# Utility_Micro_v157.net
KiCad netlist of a schematic drawn in EAGLE
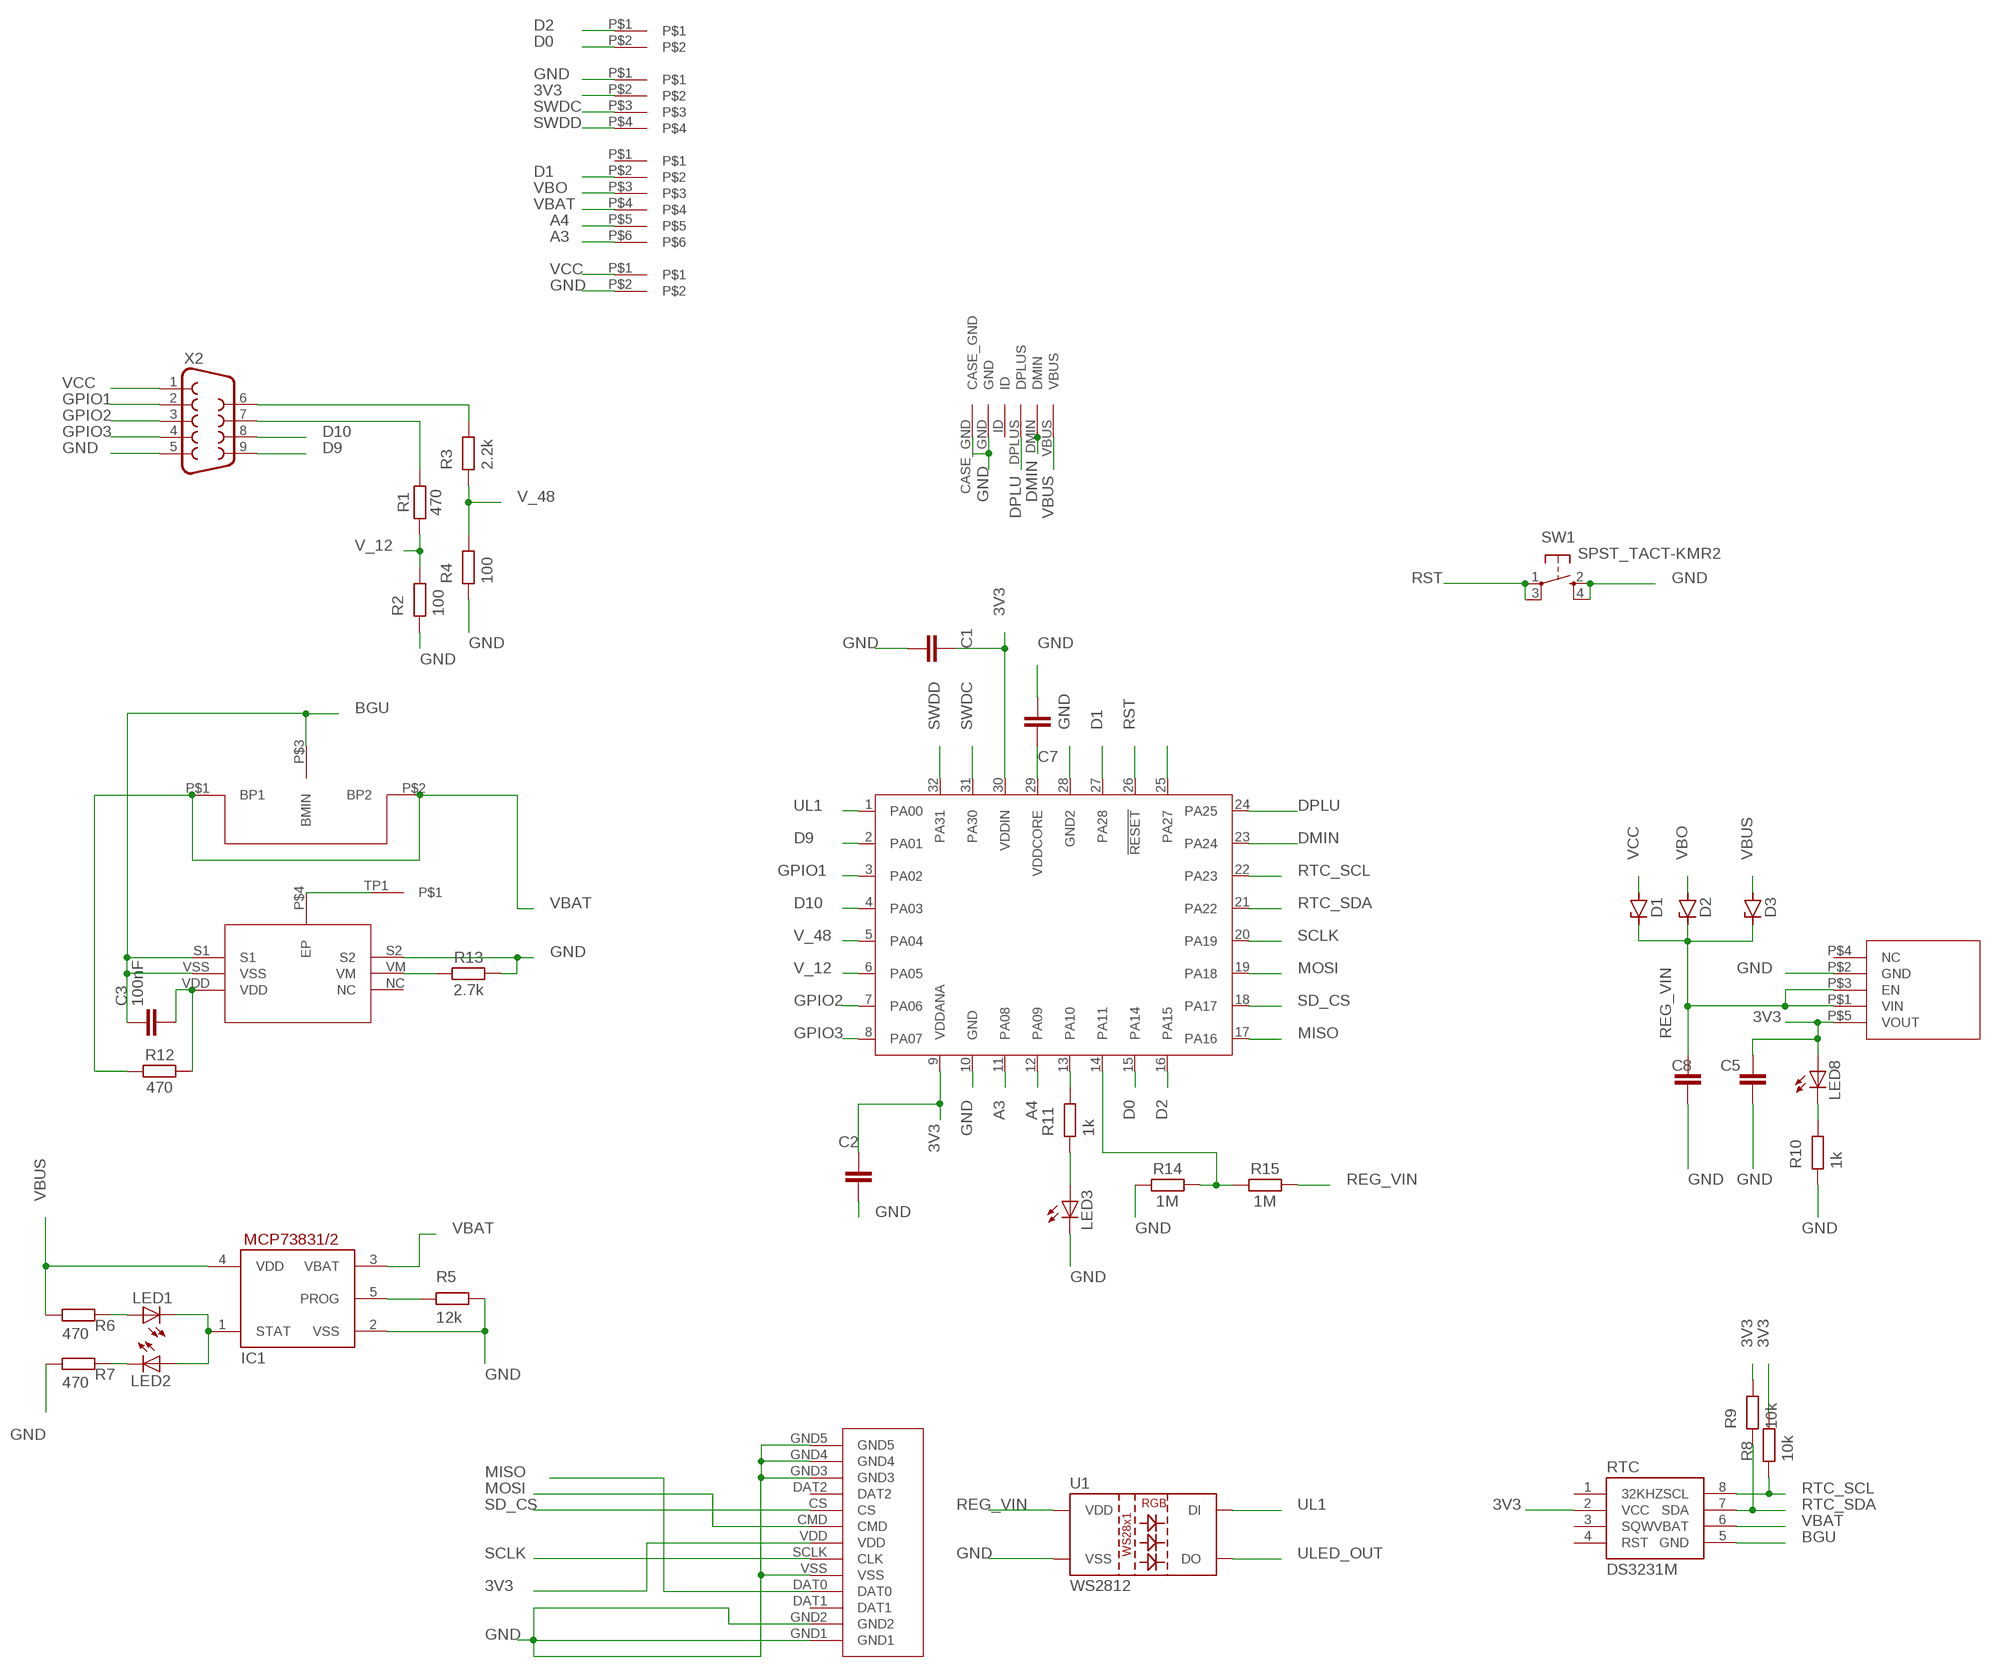
[diagram p0: schematic, sheet 1]

(export (version "E")
  (design (tool "Eeschema 10.0.6"))
  (components
    (comp (ref "ATSAMD21")
      (value "ATSAMD21TQFP")
      (footprint "eagle-import:TQFP32-08")
      (fields (field (name "MANUFACTURER") "Microchip") (field (name "MPN") "ATmega328P"))
      (libsource (lib "eagle-import") (part "ATSAMD21TQFP"))
    )
    (comp (ref "C1")
      (value "100nF")
      (footprint "eagle-import:CAPC1608X85")
      (libsource (lib "eagle-import") (part "CCHIP-0603(1608-METRIC)_"))
    )
    (comp (ref "C2")
      (value "100nF")
      (footprint "eagle-import:CAPC1608X85")
      (libsource (lib "eagle-import") (part "CCHIP-0603(1608-METRIC)_"))
    )
    (comp (ref "C3")
      (value "100nF")
      (footprint "eagle-import:CAPC1608X85")
      (libsource (lib "eagle-import") (part "CCHIP-0603(1608-METRIC)_"))
    )
    (comp (ref "C5")
      (value "10uF")
      (footprint "eagle-import:CAPC1608X85")
      (libsource (lib "eagle-import") (part "CCHIP-0603(1608-METRIC)_"))
    )
    (comp (ref "C7")
      (value "1uF")
      (footprint "eagle-import:CAPC1608X85")
      (libsource (lib "eagle-import") (part "CCHIP-0603(1608-METRIC)_"))
    )
    (comp (ref "C8")
      (value "10uF")
      (footprint "eagle-import:CAPC1608X85")
      (libsource (lib "eagle-import") (part "CCHIP-0603(1608-METRIC)_"))
    )
    (comp (ref "D1")
      (value "SCHOTTKY_MBR0520LT1GDO-219-AB(SOD123F)")
      (footprint "eagle-import:SODFL3718X115")
      (fields (field (name "MANUFACTURER") "ON Semiconductor") (field (name "MPN") "MBR0520LT1G"))
      (libsource (lib "eagle-import") (part "SCHOTTKY_DO-219-AB(SOD123F)MBR0520LT1G"))
    )
    (comp (ref "D2")
      (value "SCHOTTKY_MBR0520LT1GDO-219-AB(SOD123F)")
      (footprint "eagle-import:SODFL3718X115")
      (fields (field (name "MANUFACTURER") "ON Semiconductor") (field (name "MPN") "MBR0520LT1G"))
      (libsource (lib "eagle-import") (part "SCHOTTKY_DO-219-AB(SOD123F)MBR0520LT1G"))
    )
    (comp (ref "D3")
      (value "SCHOTTKY_MBR0520LT1GDO-219-AB(SOD123F)")
      (footprint "eagle-import:SODFL3718X115")
      (fields (field (name "MANUFACTURER") "ON Semiconductor") (field (name "MPN") "MBR0520LT1G"))
      (libsource (lib "eagle-import") (part "SCHOTTKY_DO-219-AB(SOD123F)MBR0520LT1G"))
    )
    (comp (ref "IC1")
      (value "MCP73831/OT")
      (footprint "eagle-import:SOT23-5L")
      (libsource (lib "eagle-import") (part "MCP73831/OT"))
    )
    (comp (ref "LED1")
      (value "LEDCHIP-LED0603")
      (footprint "eagle-import:CHIP-LED0603")
      (libsource (lib "eagle-import") (part "LEDCHIP-LED0603"))
    )
    (comp (ref "LED2")
      (value "LEDCHIP-LED0603")
      (footprint "eagle-import:CHIP-LED0603")
      (libsource (lib "eagle-import") (part "LEDCHIP-LED0603"))
    )
    (comp (ref "LED3")
      (value "LEDCHIP-LED0603")
      (footprint "eagle-import:CHIP-LED0603")
      (libsource (lib "eagle-import") (part "LEDCHIP-LED0603"))
    )
    (comp (ref "LED8")
      (value "LEDCHIP-LED0603")
      (footprint "eagle-import:CHIP-LED0603")
      (libsource (lib "eagle-import") (part "LEDCHIP-LED0603"))
    )
    (comp (ref "R1")
      (value "470")
      (footprint "eagle-import:RESC1608X60")
      (libsource (lib "eagle-import") (part "RCHIP-0603(1608-METRIC)_"))
    )
    (comp (ref "R2")
      (value "100")
      (footprint "eagle-import:RESC1608X60")
      (libsource (lib "eagle-import") (part "RCHIP-0603(1608-METRIC)_"))
    )
    (comp (ref "R3")
      (value "2.2k")
      (footprint "eagle-import:RESC1608X60")
      (libsource (lib "eagle-import") (part "RCHIP-0603(1608-METRIC)_"))
    )
    (comp (ref "R4")
      (value "100")
      (footprint "eagle-import:RESC1608X60")
      (libsource (lib "eagle-import") (part "RCHIP-0603(1608-METRIC)_"))
    )
    (comp (ref "R5")
      (value "12k")
      (footprint "eagle-import:RESC1608X60")
      (libsource (lib "eagle-import") (part "RCHIP-0603(1608-METRIC)_"))
    )
    (comp (ref "R6")
      (value "470")
      (footprint "eagle-import:RESC1608X60")
      (libsource (lib "eagle-import") (part "RCHIP-0603(1608-METRIC)_"))
    )
    (comp (ref "R7")
      (value "470")
      (footprint "eagle-import:RESC1608X60")
      (libsource (lib "eagle-import") (part "RCHIP-0603(1608-METRIC)_"))
    )
    (comp (ref "R8")
      (value "10k")
      (footprint "eagle-import:RESC1608X60")
      (libsource (lib "eagle-import") (part "RCHIP-0603(1608-METRIC)_"))
    )
    (comp (ref "R9")
      (value "10k")
      (footprint "eagle-import:RESC1608X60")
      (libsource (lib "eagle-import") (part "RCHIP-0603(1608-METRIC)_"))
    )
    (comp (ref "R10")
      (value "1k")
      (footprint "eagle-import:RESC1608X60")
      (libsource (lib "eagle-import") (part "RCHIP-0603(1608-METRIC)_"))
    )
    (comp (ref "R11")
      (value "1k")
      (footprint "eagle-import:RESC1608X60")
      (libsource (lib "eagle-import") (part "RCHIP-0603(1608-METRIC)_"))
    )
    (comp (ref "R12")
      (value "470")
      (footprint "eagle-import:RESC1608X60")
      (libsource (lib "eagle-import") (part "Resistor_16378527_RCHIP-0603(1608-METRIC)_"))
    )
    (comp (ref "R13")
      (value "2.7k")
      (footprint "eagle-import:RESC1608X60")
      (libsource (lib "eagle-import") (part "Resistor_16378527_RCHIP-0603(1608-METRIC)_"))
    )
    (comp (ref "R14")
      (value "1M")
      (footprint "eagle-import:RESC1608X60")
      (libsource (lib "eagle-import") (part "Resistor_16378527_RCHIP-0603(1608-METRIC)_"))
    )
    (comp (ref "R15")
      (value "1M")
      (footprint "eagle-import:RESC1608X60")
      (libsource (lib "eagle-import") (part "Resistor_16378527_RCHIP-0603(1608-METRIC)_"))
    )
    (comp (ref "RTC")
      (value "DS3231M")
      (footprint "eagle-import:SO08")
      (libsource (lib "eagle-import") (part "DS3231M"))
    )
    (comp (ref "SW1")
      (value "SPST_TACT-KMR2")
      (footprint "eagle-import:KMR2")
      (libsource (lib "eagle-import") (part "SPST_TACT-KMR2"))
    )
    (comp (ref "U$1")
      (value "AP9221")
      (footprint "eagle-import:AP9221_FOOTPRINT")
      (libsource (lib "eagle-import") (part "AP9221"))
    )
    (comp (ref "U$2")
      (value "MOLEX_MICRO_USB")
      (footprint "eagle-import:MOLEX_MICRO_USB")
      (libsource (lib "eagle-import") (part "MOLEX_MICRO_USB"))
    )
    (comp (ref "U$3")
      (value "AP2112")
      (footprint "eagle-import:SOT-25")
      (libsource (lib "eagle-import") (part "AP2112"))
    )
    (comp (ref "U$4")
      (value "LIR2450H")
      (footprint "eagle-import:BC-2005")
      (libsource (lib "eagle-import") (part "LIR2450H"))
    )
    (comp (ref "U$5")
      (value "TP_SMALL_6_DEVICE")
      (footprint "eagle-import:TP_SMALL_6")
      (libsource (lib "eagle-import") (part "TP_SMALL_6_DEVICE"))
    )
    (comp (ref "U$6")
      (value "SMALL_MICRO_SD")
      (footprint "eagle-import:MICRO_SD_SMALL")
      (libsource (lib "eagle-import") (part "SMALL_MICRO_SD"))
    )
    (comp (ref "U$7")
      (value "TP_2")
      (footprint "eagle-import:TP_2")
      (libsource (lib "eagle-import") (part "TP_2"))
    )
    (comp (ref "U$8")
      (value "TP_SMALL_4_DEVICE")
      (footprint "eagle-import:TP_SMALL_4")
      (libsource (lib "eagle-import") (part "TP_SMALL_4_DEVICE"))
    )
    (comp (ref "U$9")
      (value "TP_2")
      (footprint "eagle-import:TP_2")
      (libsource (lib "eagle-import") (part "TP_2"))
    )
    (comp (ref "U$10")
      (value "SINGLE-SMD")
      (footprint "eagle-import:SINGLE-SMD")
      (libsource (lib "eagle-import") (part "SINGLE-SMD"))
    )
    (comp (ref "U1")
      (value "WS2812")
      (footprint "eagle-import:LED-TRICOLOR-5050-IC")
      (libsource (lib "eagle-import") (part "WS2812{dblquote}"))
    )
    (comp (ref "X2")
      (value "F09D")
      (footprint "eagle-import:F09D")
      (libsource (lib "eagle-import") (part "F09D"))
    )
  )
  (nets
    (net (code "1") (name "/3V3") (class "Default")
      (node (ref "ATSAMD21") (pin "30") (pinfunction "VDDIN_30") (pintype "power_in"))
      (node (ref "ATSAMD21") (pin "9") (pinfunction "VDDANA_9") (pintype "power_in"))
      (node (ref "C1") (pin "2") (pinfunction "2_2") (pintype "passive"))
      (node (ref "C2") (pin "2") (pinfunction "2_2") (pintype "passive"))
      (node (ref "C5") (pin "1") (pinfunction "1_1") (pintype "passive"))
      (node (ref "LED8") (pin "A") (pinfunction "A_A") (pintype "passive"))
      (node (ref "R8") (pin "2") (pinfunction "2_2") (pintype "passive"))
      (node (ref "R9") (pin "2") (pinfunction "2_2") (pintype "passive"))
      (node (ref "RTC") (pin "2") (pinfunction "VCC_2") (pintype "power_in"))
      (node (ref "U$3") (pin "P$5") (pinfunction "VOUT_P$5") (pintype "power_in"))
      (node (ref "U$6") (pin "VDD") (pinfunction "VDD_VDD") (pintype "bidirectional"))
      (node (ref "U$8") (pin "P$2") (pinfunction "P$2_P$2") (pintype "bidirectional"))
    )
    (net (code "2") (name "/A3") (class "Default")
      (node (ref "ATSAMD21") (pin "11") (pinfunction "PA08_11") (pintype "bidirectional"))
      (node (ref "U$5") (pin "P$6") (pinfunction "P$6_P$6") (pintype "bidirectional"))
    )
    (net (code "3") (name "/A4") (class "Default")
      (node (ref "ATSAMD21") (pin "12") (pinfunction "PA09_12") (pintype "bidirectional"))
      (node (ref "U$5") (pin "P$5") (pinfunction "P$5_P$5") (pintype "bidirectional"))
    )
    (net (code "4") (name "/BGU") (class "Default")
      (node (ref "C3") (pin "1") (pinfunction "1_1") (pintype "passive"))
      (node (ref "RTC") (pin "5") (pinfunction "GND_5") (pintype "power_in"))
      (node (ref "U$1") (pin "S1") (pinfunction "S1_S1") (pintype "bidirectional"))
      (node (ref "U$1") (pin "VSS") (pinfunction "VSS_VSS") (pintype "bidirectional"))
      (node (ref "U$4") (pin "P$3") (pinfunction "BMIN_P$3") (pintype "bidirectional"))
    )
    (net (code "5") (name "/D0") (class "Default")
      (node (ref "ATSAMD21") (pin "15") (pinfunction "PA14_15") (pintype "bidirectional"))
      (node (ref "U$7") (pin "P$2") (pinfunction "P$2_P$2") (pintype "bidirectional"))
    )
    (net (code "6") (name "/D1") (class "Default")
      (node (ref "ATSAMD21") (pin "27") (pinfunction "PA28_27") (pintype "bidirectional"))
      (node (ref "U$5") (pin "P$2") (pinfunction "P$2_P$2") (pintype "bidirectional"))
    )
    (net (code "7") (name "/D2") (class "Default")
      (node (ref "ATSAMD21") (pin "16") (pinfunction "PA15_16") (pintype "bidirectional"))
      (node (ref "U$7") (pin "P$1") (pinfunction "P$1_P$1") (pintype "bidirectional"))
    )
    (net (code "8") (name "/D9") (class "Default")
      (node (ref "ATSAMD21") (pin "2") (pinfunction "PA01_2") (pintype "bidirectional"))
      (node (ref "X2") (pin "9") (pinfunction "9_9") (pintype "passive"))
    )
    (net (code "9") (name "/D10") (class "Default")
      (node (ref "ATSAMD21") (pin "4") (pinfunction "PA03_4") (pintype "bidirectional"))
      (node (ref "X2") (pin "8") (pinfunction "8_8") (pintype "passive"))
    )
    (net (code "10") (name "/DMIN") (class "Default")
      (node (ref "ATSAMD21") (pin "23") (pinfunction "PA24_23") (pintype "bidirectional"))
      (node (ref "U$2") (pin "DMIN") (pinfunction "DMIN_DMIN") (pintype "bidirectional"))
    )
    (net (code "11") (name "/DPLU") (class "Default")
      (node (ref "ATSAMD21") (pin "24") (pinfunction "PA25_24") (pintype "bidirectional"))
      (node (ref "U$2") (pin "DPLUS") (pinfunction "DPLUS_DPLUS") (pintype "bidirectional"))
    )
    (net (code "12") (name "/GND") (class "Default")
      (node (ref "ATSAMD21") (pin "10") (pinfunction "GND_10") (pintype "passive"))
      (node (ref "ATSAMD21") (pin "28") (pinfunction "GND2_28") (pintype "passive"))
      (node (ref "C1") (pin "1") (pinfunction "1_1") (pintype "passive"))
      (node (ref "C2") (pin "1") (pinfunction "1_1") (pintype "passive"))
      (node (ref "C5") (pin "2") (pinfunction "2_2") (pintype "passive"))
      (node (ref "C7") (pin "1") (pinfunction "1_1") (pintype "passive"))
      (node (ref "C8") (pin "2") (pinfunction "2_2") (pintype "passive"))
      (node (ref "IC1") (pin "2") (pinfunction "VSS_2") (pintype "power_in"))
      (node (ref "LED3") (pin "C") (pinfunction "C_C") (pintype "passive"))
      (node (ref "R10") (pin "1") (pinfunction "1_1") (pintype "passive"))
      (node (ref "R13") (pin "2") (pinfunction "2_2") (pintype "passive"))
      (node (ref "R14") (pin "1") (pinfunction "1_1") (pintype "passive"))
      (node (ref "R2") (pin "1") (pinfunction "1_1") (pintype "passive"))
      (node (ref "R4") (pin "1") (pinfunction "1_1") (pintype "passive"))
      (node (ref "R5") (pin "2") (pinfunction "2_2") (pintype "passive"))
      (node (ref "R7") (pin "1") (pinfunction "1_1") (pintype "passive"))
      (node (ref "SW1") (pin "2") (pinfunction "S_2") (pintype "passive"))
      (node (ref "SW1") (pin "4") (pinfunction "S1_4") (pintype "passive"))
      (node (ref "U$1") (pin "S2") (pinfunction "S2_S2") (pintype "bidirectional"))
      (node (ref "U$2") (pin "CASE_GND") (pinfunction "CASE_GND_CASE_GND") (pintype "bidirectional"))
      (node (ref "U$2") (pin "GND") (pinfunction "GND_GND") (pintype "bidirectional"))
      (node (ref "U$3") (pin "P$2") (pinfunction "GND_P$2") (pintype "passive"))
      (node (ref "U$6") (pin "GND1") (pinfunction "GND1_GND1") (pintype "bidirectional"))
      (node (ref "U$6") (pin "GND2") (pinfunction "GND2_GND2") (pintype "bidirectional"))
      (node (ref "U$6") (pin "GND3") (pinfunction "GND3_GND3") (pintype "bidirectional"))
      (node (ref "U$6") (pin "GND4") (pinfunction "GND4_GND4") (pintype "bidirectional"))
      (node (ref "U$6") (pin "GND5") (pinfunction "GND5_GND5") (pintype "bidirectional"))
      (node (ref "U$6") (pin "VSS") (pinfunction "VSS_VSS") (pintype "bidirectional"))
      (node (ref "U$8") (pin "P$1") (pinfunction "P$1_P$1") (pintype "bidirectional"))
      (node (ref "U$9") (pin "P$2") (pinfunction "P$2_P$2") (pintype "bidirectional"))
      (node (ref "U1") (pin "6") (pinfunction "VSS_6") (pintype "bidirectional"))
      (node (ref "X2") (pin "5") (pinfunction "5_5") (pintype "passive"))
    )
    (net (code "13") (name "/GPIO1") (class "Default")
      (node (ref "ATSAMD21") (pin "3") (pinfunction "PA02_3") (pintype "bidirectional"))
      (node (ref "X2") (pin "2") (pinfunction "2_2") (pintype "passive"))
    )
    (net (code "14") (name "/GPIO2") (class "Default")
      (node (ref "ATSAMD21") (pin "7") (pinfunction "PA06_7") (pintype "bidirectional"))
      (node (ref "X2") (pin "3") (pinfunction "3_3") (pintype "passive"))
    )
    (net (code "15") (name "/GPIO3") (class "Default")
      (node (ref "ATSAMD21") (pin "8") (pinfunction "PA07_8") (pintype "bidirectional"))
      (node (ref "X2") (pin "4") (pinfunction "4_4") (pintype "passive"))
    )
    (net (code "16") (name "/MISO") (class "Default")
      (node (ref "ATSAMD21") (pin "17") (pinfunction "PA16_17") (pintype "bidirectional"))
      (node (ref "U$6") (pin "DAT0") (pinfunction "DAT0_DAT0") (pintype "bidirectional"))
    )
    (net (code "17") (name "/MOSI") (class "Default")
      (node (ref "ATSAMD21") (pin "19") (pinfunction "PA18_19") (pintype "bidirectional"))
      (node (ref "U$6") (pin "CMD") (pinfunction "CMD_CMD") (pintype "bidirectional"))
    )
    (net (code "18") (name "/REG_VIN") (class "Default")
      (node (ref "C8") (pin "1") (pinfunction "1_1") (pintype "passive"))
      (node (ref "D1") (pin "2") (pinfunction "C_2") (pintype "passive"))
      (node (ref "D2") (pin "2") (pinfunction "C_2") (pintype "passive"))
      (node (ref "D3") (pin "2") (pinfunction "C_2") (pintype "passive"))
      (node (ref "R15") (pin "2") (pinfunction "2_2") (pintype "passive"))
      (node (ref "U$3") (pin "P$1") (pinfunction "VIN_P$1") (pintype "power_in"))
      (node (ref "U$3") (pin "P$3") (pinfunction "EN_P$3") (pintype "input"))
      (node (ref "U1") (pin "3") (pinfunction "VDD_3") (pintype "bidirectional"))
      (node (ref "U1") (pin "5") (pinfunction "VDD_5") (pintype "bidirectional"))
    )
    (net (code "19") (name "/RST") (class "Default")
      (node (ref "ATSAMD21") (pin "26") (pinfunction "~{RESET}_26") (pintype "bidirectional"))
      (node (ref "SW1") (pin "1") (pinfunction "P_1") (pintype "passive"))
      (node (ref "SW1") (pin "3") (pinfunction "P1_3") (pintype "passive"))
    )
    (net (code "20") (name "/RTC_SCL") (class "Default")
      (node (ref "ATSAMD21") (pin "22") (pinfunction "PA23_22") (pintype "bidirectional"))
      (node (ref "R8") (pin "1") (pinfunction "1_1") (pintype "passive"))
      (node (ref "RTC") (pin "8") (pinfunction "SCL_8") (pintype "bidirectional"))
    )
    (net (code "21") (name "/RTC_SDA") (class "Default")
      (node (ref "ATSAMD21") (pin "21") (pinfunction "PA22_21") (pintype "bidirectional"))
      (node (ref "R9") (pin "1") (pinfunction "1_1") (pintype "passive"))
      (node (ref "RTC") (pin "7") (pinfunction "SDA_7") (pintype "bidirectional"))
    )
    (net (code "22") (name "/SCLK") (class "Default")
      (node (ref "ATSAMD21") (pin "20") (pinfunction "PA19_20") (pintype "bidirectional"))
      (node (ref "U$6") (pin "SCLK") (pinfunction "CLK_SCLK") (pintype "bidirectional"))
    )
    (net (code "23") (name "/SD_CS") (class "Default")
      (node (ref "ATSAMD21") (pin "18") (pinfunction "PA17_18") (pintype "bidirectional"))
      (node (ref "U$6") (pin "CS") (pinfunction "CS_CS") (pintype "bidirectional"))
    )
    (net (code "24") (name "/SWDC") (class "Default")
      (node (ref "ATSAMD21") (pin "31") (pinfunction "PA30_31") (pintype "bidirectional"))
      (node (ref "U$8") (pin "P$3") (pinfunction "P$3_P$3") (pintype "bidirectional"))
    )
    (net (code "25") (name "/SWDD") (class "Default")
      (node (ref "ATSAMD21") (pin "32") (pinfunction "PA31_32") (pintype "bidirectional"))
      (node (ref "U$8") (pin "P$4") (pinfunction "P$4_P$4") (pintype "bidirectional"))
    )
    (net (code "26") (name "/UL1") (class "Default")
      (node (ref "ATSAMD21") (pin "1") (pinfunction "PA00_1") (pintype "bidirectional"))
      (node (ref "U1") (pin "2") (pinfunction "DI_2") (pintype "bidirectional"))
    )
    (net (code "27") (name "/ULED_OUT") (class "Default")
      (node (ref "U1") (pin "1") (pinfunction "DO_1") (pintype "bidirectional"))
    )
    (net (code "28") (name "/VBAT") (class "Default")
      (node (ref "IC1") (pin "3") (pinfunction "VBAT_3") (pintype "bidirectional"))
      (node (ref "R12") (pin "1") (pinfunction "1_1") (pintype "passive"))
      (node (ref "RTC") (pin "6") (pinfunction "VBAT_6") (pintype "power_in"))
      (node (ref "U$4") (pin "P$1") (pinfunction "BP1_P$1") (pintype "bidirectional"))
      (node (ref "U$4") (pin "P$2") (pinfunction "BP2_P$2") (pintype "bidirectional"))
      (node (ref "U$5") (pin "P$4") (pinfunction "P$4_P$4") (pintype "bidirectional"))
    )
    (net (code "29") (name "/VBO") (class "Default")
      (node (ref "D2") (pin "1") (pinfunction "A_1") (pintype "passive"))
      (node (ref "U$5") (pin "P$3") (pinfunction "P$3_P$3") (pintype "bidirectional"))
    )
    (net (code "30") (name "/VBUS") (class "Default")
      (node (ref "D3") (pin "1") (pinfunction "A_1") (pintype "passive"))
      (node (ref "IC1") (pin "4") (pinfunction "VDD_4") (pintype "power_in"))
      (node (ref "R6") (pin "1") (pinfunction "1_1") (pintype "passive"))
      (node (ref "U$2") (pin "VBUS") (pinfunction "VBUS_VBUS") (pintype "bidirectional"))
    )
    (net (code "31") (name "/VCC") (class "Default")
      (node (ref "D1") (pin "1") (pinfunction "A_1") (pintype "passive"))
      (node (ref "U$9") (pin "P$1") (pinfunction "P$1_P$1") (pintype "bidirectional"))
      (node (ref "X2") (pin "1") (pinfunction "1_1") (pintype "passive"))
    )
    (net (code "32") (name "/V_12") (class "Default")
      (node (ref "ATSAMD21") (pin "6") (pinfunction "PA05_6") (pintype "bidirectional"))
      (node (ref "R1") (pin "1") (pinfunction "1_1") (pintype "passive"))
      (node (ref "R2") (pin "2") (pinfunction "2_2") (pintype "passive"))
    )
    (net (code "33") (name "/V_48") (class "Default")
      (node (ref "ATSAMD21") (pin "5") (pinfunction "PA04_5") (pintype "bidirectional"))
      (node (ref "R3") (pin "1") (pinfunction "1_1") (pintype "passive"))
      (node (ref "R4") (pin "2") (pinfunction "2_2") (pintype "passive"))
    )
    (net (code "34") (name "Net-(ATSAMD21-PA10)") (class "Default")
      (node (ref "ATSAMD21") (pin "13") (pinfunction "PA10_13") (pintype "bidirectional"))
      (node (ref "R11") (pin "2") (pinfunction "2_2") (pintype "passive"))
    )
    (net (code "35") (name "Net-(ATSAMD21-PA11)") (class "Default")
      (node (ref "ATSAMD21") (pin "14") (pinfunction "PA11_14") (pintype "bidirectional"))
      (node (ref "R14") (pin "2") (pinfunction "2_2") (pintype "passive"))
      (node (ref "R15") (pin "1") (pinfunction "1_1") (pintype "passive"))
    )
    (net (code "36") (name "Net-(ATSAMD21-VDDCORE)") (class "Default")
      (node (ref "ATSAMD21") (pin "29") (pinfunction "VDDCORE_29") (pintype "power_in"))
      (node (ref "C7") (pin "2") (pinfunction "2_2") (pintype "passive"))
    )
    (net (code "37") (name "Net-(C3-Pad2)") (class "Default")
      (node (ref "C3") (pin "2") (pinfunction "2_2") (pintype "passive"))
      (node (ref "R12") (pin "2") (pinfunction "2_2") (pintype "passive"))
      (node (ref "U$1") (pin "VDD") (pinfunction "VDD_VDD") (pintype "bidirectional"))
    )
    (net (code "38") (name "Net-(IC1-PROG)") (class "Default")
      (node (ref "IC1") (pin "5") (pinfunction "PROG_5") (pintype "input"))
      (node (ref "R5") (pin "1") (pinfunction "1_1") (pintype "passive"))
    )
    (net (code "39") (name "Net-(IC1-STAT)") (class "Default")
      (node (ref "IC1") (pin "1") (pinfunction "STAT_1") (pintype "output"))
      (node (ref "LED1") (pin "C") (pinfunction "C_C") (pintype "passive"))
      (node (ref "LED2") (pin "A") (pinfunction "A_A") (pintype "passive"))
    )
    (net (code "40") (name "Net-(LED1-PadA)") (class "Default")
      (node (ref "LED1") (pin "A") (pinfunction "A_A") (pintype "passive"))
      (node (ref "R6") (pin "2") (pinfunction "2_2") (pintype "passive"))
    )
    (net (code "41") (name "Net-(LED2-PadC)") (class "Default")
      (node (ref "LED2") (pin "C") (pinfunction "C_C") (pintype "passive"))
      (node (ref "R7") (pin "2") (pinfunction "2_2") (pintype "passive"))
    )
    (net (code "42") (name "Net-(LED3-PadA)") (class "Default")
      (node (ref "LED3") (pin "A") (pinfunction "A_A") (pintype "passive"))
      (node (ref "R11") (pin "1") (pinfunction "1_1") (pintype "passive"))
    )
    (net (code "43") (name "Net-(LED8-PadC)") (class "Default")
      (node (ref "LED8") (pin "C") (pinfunction "C_C") (pintype "passive"))
      (node (ref "R10") (pin "2") (pinfunction "2_2") (pintype "passive"))
    )
    (net (code "44") (name "Net-(R1-Pad2)") (class "Default")
      (node (ref "R1") (pin "2") (pinfunction "2_2") (pintype "passive"))
      (node (ref "X2") (pin "7") (pinfunction "7_7") (pintype "passive"))
    )
    (net (code "45") (name "Net-(R3-Pad2)") (class "Default")
      (node (ref "R3") (pin "2") (pinfunction "2_2") (pintype "passive"))
      (node (ref "X2") (pin "6") (pinfunction "6_6") (pintype "passive"))
    )
    (net (code "46") (name "Net-(R13-Pad1)") (class "Default")
      (node (ref "R13") (pin "1") (pinfunction "1_1") (pintype "passive"))
      (node (ref "U$1") (pin "VM") (pinfunction "VM_VM") (pintype "bidirectional"))
    )
    (net (code "47") (name "Net-(U$1-EP)") (class "Default")
      (node (ref "U$1") (pin "P$4") (pinfunction "EP_P$4") (pintype "bidirectional"))
      (node (ref "U$10") (pin "TP1") (pinfunction "P$1_TP1") (pintype "bidirectional"))
    )
    (net (code "48") (name "unconnected-(ATSAMD21-PA27-Pad25)") (class "Default")
      (node (ref "ATSAMD21") (pin "25") (pinfunction "PA27_25") (pintype "bidirectional"))
    )
    (net (code "49") (name "unconnected-(RTC-32KHZ-Pad1)") (class "Default")
      (node (ref "RTC") (pin "1") (pinfunction "32KHZ_1") (pintype "output"))
    )
    (net (code "50") (name "unconnected-(RTC-RST-Pad4)") (class "Default")
      (node (ref "RTC") (pin "4") (pinfunction "RST_4") (pintype "bidirectional"))
    )
    (net (code "51") (name "unconnected-(RTC-SQW-Pad3)") (class "Default")
      (node (ref "RTC") (pin "3") (pinfunction "SQW_3") (pintype "output"))
    )
    (net (code "52") (name "unconnected-(U$1-PadNC)") (class "Default")
      (node (ref "U$1") (pin "NC") (pinfunction "NC_NC") (pintype "bidirectional"))
    )
    (net (code "53") (name "unconnected-(U$2-PadID)") (class "Default")
      (node (ref "U$2") (pin "ID") (pinfunction "ID_ID") (pintype "bidirectional"))
    )
    (net (code "54") (name "unconnected-(U$3-NC-PadP$4)") (class "Default")
      (node (ref "U$3") (pin "P$4") (pinfunction "NC_P$4") (pintype "no_connect"))
    )
    (net (code "55") (name "unconnected-(U$5-PadP$1)") (class "Default")
      (node (ref "U$5") (pin "P$1") (pinfunction "P$1_P$1") (pintype "bidirectional"))
    )
    (net (code "56") (name "unconnected-(U$6-PadDAT1)") (class "Default")
      (node (ref "U$6") (pin "DAT1") (pinfunction "DAT1_DAT1") (pintype "bidirectional"))
    )
    (net (code "57") (name "unconnected-(U$6-PadDAT2)") (class "Default")
      (node (ref "U$6") (pin "DAT2") (pinfunction "DAT2_DAT2") (pintype "bidirectional"))
    )
  )
)
